# P10_HDMI_Framer.net
KiCad netlist of a schematic drawn in Altium Designer
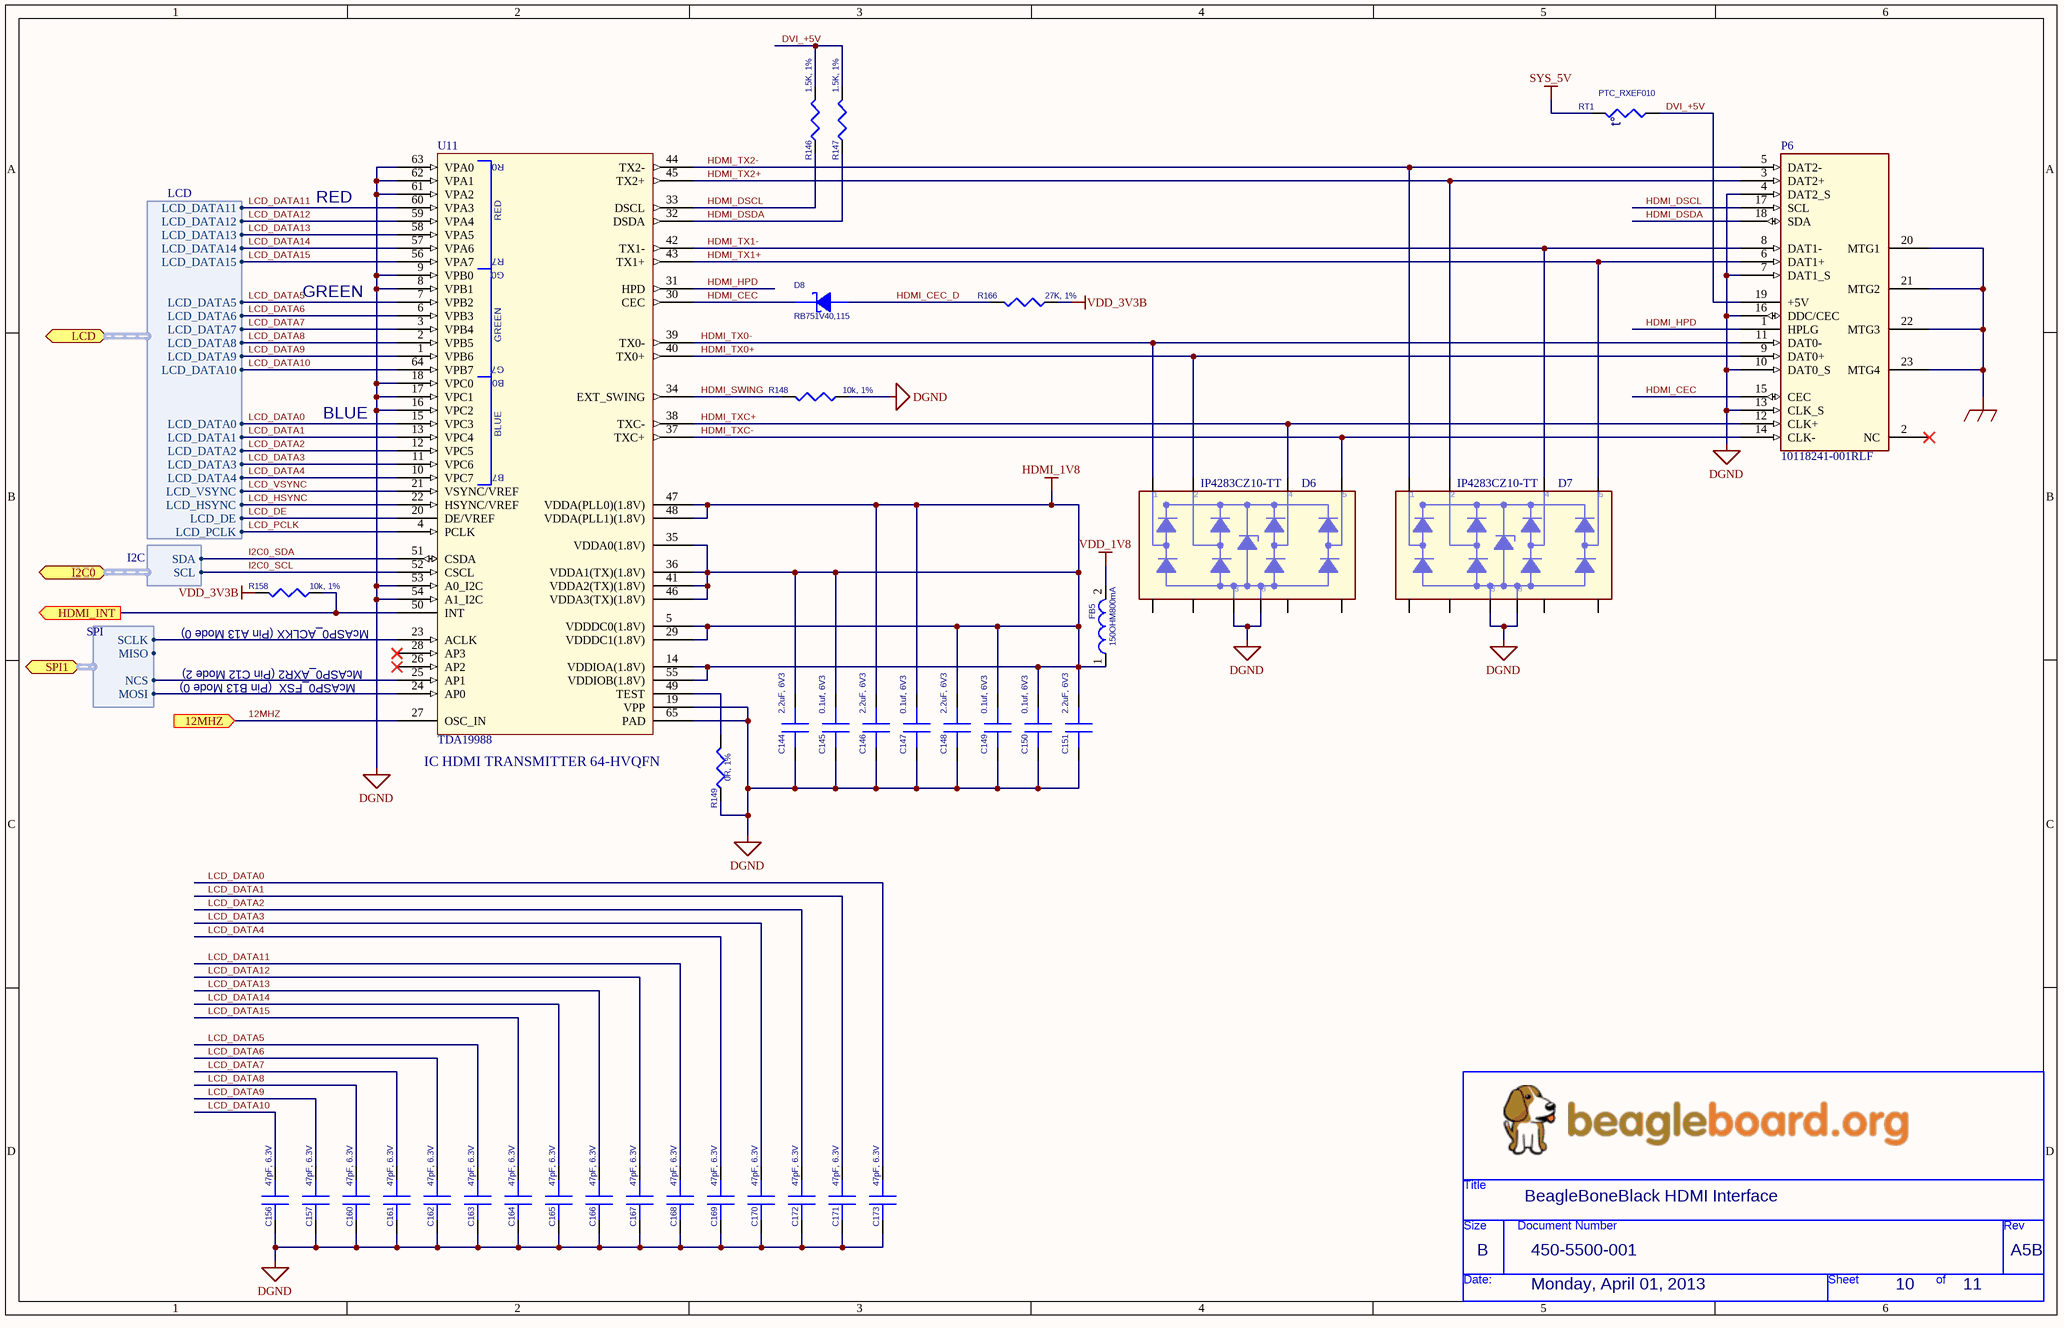
[diagram p0: P10_HDMI Framer.SchDoc]

(export (version "E")
  (design (tool "Eeschema 10.0.6"))
  (components
    (comp (ref "C144")
      (value "2.2uF, 6V3")
      (footprint "402")
      (description "CAP CER 2.2UF 6.3V 10% X5R 0402")
      (fields
        (field (name "MANUFACTURER") "TDK Corporation")
        (field (name "MANUFACTURER PART NUMBER") "C1005X5R0J225K050BC")
      )
      (libsource (lib "BEAGLEBONEBLACK_REV A5B") (part "CAP SMD"))
    )
    (comp (ref "C145")
      (value "0.1uf, 6V3")
      (footprint "402")
      (description "CAP CER 0.1UF 6.3V 10% X5R 0402")
      (fields
        (field (name "MANUFACTURER") "TDK Corporation")
        (field (name "MANUFACTURER PART NUMBER") "C1005X5R0J104K050BA")
      )
      (libsource (lib "BEAGLEBONEBLACK_REV A5B") (part "CAP SMD"))
    )
    (comp (ref "C146")
      (value "2.2uF, 6V3")
      (footprint "402")
      (description "CAP CER 2.2UF 6.3V 10% X5R 0402")
      (fields
        (field (name "MANUFACTURER") "TDK Corporation")
        (field (name "MANUFACTURER PART NUMBER") "C1005X5R0J225K050BC")
      )
      (libsource (lib "BEAGLEBONEBLACK_REV A5B") (part "CAP SMD"))
    )
    (comp (ref "C147")
      (value "0.1uf, 6V3")
      (footprint "402")
      (description "CAP CER 0.1UF 6.3V 10% X5R 0402")
      (fields
        (field (name "MANUFACTURER") "TDK Corporation")
        (field (name "MANUFACTURER PART NUMBER") "C1005X5R0J104K050BA")
      )
      (libsource (lib "BEAGLEBONEBLACK_REV A5B") (part "CAP SMD"))
    )
    (comp (ref "C148")
      (value "2.2uF, 6V3")
      (footprint "402")
      (description "CAP CER 2.2UF 6.3V 10% X5R 0402")
      (fields
        (field (name "MANUFACTURER") "TDK Corporation")
        (field (name "MANUFACTURER PART NUMBER") "C1005X5R0J225K050BC")
      )
      (libsource (lib "BEAGLEBONEBLACK_REV A5B") (part "CAP SMD"))
    )
    (comp (ref "C149")
      (value "0.1uf, 6V3")
      (footprint "402")
      (description "CAP CER 0.1UF 6.3V 10% X5R 0402")
      (fields
        (field (name "MANUFACTURER") "TDK Corporation")
        (field (name "MANUFACTURER PART NUMBER") "C1005X5R0J104K050BA")
      )
      (libsource (lib "BEAGLEBONEBLACK_REV A5B") (part "CAP SMD"))
    )
    (comp (ref "C150")
      (value "0.1uf, 6V3")
      (footprint "402")
      (description "CAP CER 0.1UF 6.3V 10% X5R 0402")
      (fields
        (field (name "MANUFACTURER") "TDK Corporation")
        (field (name "MANUFACTURER PART NUMBER") "C1005X5R0J104K050BA")
      )
      (libsource (lib "BEAGLEBONEBLACK_REV A5B") (part "CAP SMD"))
    )
    (comp (ref "C151")
      (value "2.2uF, 6V3")
      (footprint "402")
      (description "CAP CER 2.2UF 6.3V 10% X5R 0402")
      (fields
        (field (name "MANUFACTURER") "TDK Corporation")
        (field (name "MANUFACTURER PART NUMBER") "C1005X5R0J225K050BC")
      )
      (libsource (lib "BEAGLEBONEBLACK_REV A5B") (part "CAP SMD"))
    )
    (comp (ref "C156")
      (value "47pF, 6.3V")
      (footprint "402")
      (description "CAP CER 47PF 50V 5% NP0 0402")
      (fields
        (field (name "MANUFACTURER") "TDK Corporation")
        (field (name "MANUFACTURER PART NUMBER") "C1005C0G1H470J050BA")
      )
      (libsource (lib "BEAGLEBONEBLACK_REV A5B") (part "CAP SMD"))
    )
    (comp (ref "C157")
      (value "47pF, 6.3V")
      (footprint "402")
      (description "CAP CER 47PF 50V 5% NP0 0402")
      (fields
        (field (name "MANUFACTURER") "TDK Corporation")
        (field (name "MANUFACTURER PART NUMBER") "C1005C0G1H470J050BA")
      )
      (libsource (lib "BEAGLEBONEBLACK_REV A5B") (part "CAP SMD"))
    )
    (comp (ref "C160")
      (value "47pF, 6.3V")
      (footprint "402")
      (description "CAP CER 47PF 50V 5% NP0 0402")
      (fields
        (field (name "MANUFACTURER") "TDK Corporation")
        (field (name "MANUFACTURER PART NUMBER") "C1005C0G1H470J050BA")
      )
      (libsource (lib "BEAGLEBONEBLACK_REV A5B") (part "CAP SMD"))
    )
    (comp (ref "C161")
      (value "47pF, 6.3V")
      (footprint "402")
      (description "CAP CER 47PF 50V 5% NP0 0402")
      (fields
        (field (name "MANUFACTURER") "TDK Corporation")
        (field (name "MANUFACTURER PART NUMBER") "C1005C0G1H470J050BA")
      )
      (libsource (lib "BEAGLEBONEBLACK_REV A5B") (part "CAP SMD"))
    )
    (comp (ref "C162")
      (value "47pF, 6.3V")
      (footprint "402")
      (description "CAP CER 47PF 50V 5% NP0 0402")
      (fields
        (field (name "MANUFACTURER") "TDK Corporation")
        (field (name "MANUFACTURER PART NUMBER") "C1005C0G1H470J050BA")
      )
      (libsource (lib "BEAGLEBONEBLACK_REV A5B") (part "CAP SMD"))
    )
    (comp (ref "C163")
      (value "47pF, 6.3V")
      (footprint "402")
      (description "CAP CER 47PF 50V 5% NP0 0402")
      (fields
        (field (name "MANUFACTURER") "TDK Corporation")
        (field (name "MANUFACTURER PART NUMBER") "C1005C0G1H470J050BA")
      )
      (libsource (lib "BEAGLEBONEBLACK_REV A5B") (part "CAP SMD"))
    )
    (comp (ref "C164")
      (value "47pF, 6.3V")
      (footprint "402")
      (description "CAP CER 47PF 50V 5% NP0 0402")
      (fields
        (field (name "MANUFACTURER") "TDK Corporation")
        (field (name "MANUFACTURER PART NUMBER") "C1005C0G1H470J050BA")
      )
      (libsource (lib "BEAGLEBONEBLACK_REV A5B") (part "CAP SMD"))
    )
    (comp (ref "C165")
      (value "47pF, 6.3V")
      (footprint "402")
      (description "CAP CER 47PF 50V 5% NP0 0402")
      (fields
        (field (name "MANUFACTURER") "TDK Corporation")
        (field (name "MANUFACTURER PART NUMBER") "C1005C0G1H470J050BA")
      )
      (libsource (lib "BEAGLEBONEBLACK_REV A5B") (part "CAP SMD"))
    )
    (comp (ref "C166")
      (value "47pF, 6.3V")
      (footprint "402")
      (description "CAP CER 47PF 50V 5% NP0 0402")
      (fields
        (field (name "MANUFACTURER") "TDK Corporation")
        (field (name "MANUFACTURER PART NUMBER") "C1005C0G1H470J050BA")
      )
      (libsource (lib "BEAGLEBONEBLACK_REV A5B") (part "CAP SMD"))
    )
    (comp (ref "C167")
      (value "47pF, 6.3V")
      (footprint "402")
      (description "CAP CER 47PF 50V 5% NP0 0402")
      (fields
        (field (name "MANUFACTURER") "TDK Corporation")
        (field (name "MANUFACTURER PART NUMBER") "C1005C0G1H470J050BA")
      )
      (libsource (lib "BEAGLEBONEBLACK_REV A5B") (part "CAP SMD"))
    )
    (comp (ref "C168")
      (value "47pF, 6.3V")
      (footprint "402")
      (description "CAP CER 47PF 50V 5% NP0 0402")
      (fields
        (field (name "MANUFACTURER") "TDK Corporation")
        (field (name "MANUFACTURER PART NUMBER") "C1005C0G1H470J050BA")
      )
      (libsource (lib "BEAGLEBONEBLACK_REV A5B") (part "CAP SMD"))
    )
    (comp (ref "C169")
      (value "47pF, 6.3V")
      (footprint "402")
      (description "CAP CER 47PF 50V 5% NP0 0402")
      (fields
        (field (name "MANUFACTURER") "TDK Corporation")
        (field (name "MANUFACTURER PART NUMBER") "C1005C0G1H470J050BA")
      )
      (libsource (lib "BEAGLEBONEBLACK_REV A5B") (part "CAP SMD"))
    )
    (comp (ref "C170")
      (value "47pF, 6.3V")
      (footprint "402")
      (description "CAP CER 47PF 50V 5% NP0 0402")
      (fields
        (field (name "MANUFACTURER") "TDK Corporation")
        (field (name "MANUFACTURER PART NUMBER") "C1005C0G1H470J050BA")
      )
      (libsource (lib "BEAGLEBONEBLACK_REV A5B") (part "CAP SMD"))
    )
    (comp (ref "C171")
      (value "47pF, 6.3V")
      (footprint "402")
      (description "CAP CER 47PF 50V 5% NP0 0402")
      (fields
        (field (name "MANUFACTURER") "TDK Corporation")
        (field (name "MANUFACTURER PART NUMBER") "C1005C0G1H470J050BA")
      )
      (libsource (lib "BEAGLEBONEBLACK_REV A5B") (part "CAP SMD"))
    )
    (comp (ref "C172")
      (value "47pF, 6.3V")
      (footprint "402")
      (description "CAP CER 47PF 50V 5% NP0 0402")
      (fields
        (field (name "MANUFACTURER") "TDK Corporation")
        (field (name "MANUFACTURER PART NUMBER") "C1005C0G1H470J050BA")
      )
      (libsource (lib "BEAGLEBONEBLACK_REV A5B") (part "CAP SMD"))
    )
    (comp (ref "C173")
      (value "47pF, 6.3V")
      (footprint "402")
      (description "CAP CER 47PF 50V 5% NP0 0402")
      (fields
        (field (name "MANUFACTURER") "TDK Corporation")
        (field (name "MANUFACTURER PART NUMBER") "C1005C0G1H470J050BA")
      )
      (libsource (lib "BEAGLEBONEBLACK_REV A5B") (part "CAP SMD"))
    )
    (comp (ref "D6")
      (value "IP4283CZ10-TT")
      (footprint "TSSOP10")
      (description "DIODE ESD PROT HDMI 10TSSOP")
      (fields
        (field (name "MANUFACTURER") "NXP Semiconductors")
        (field (name "MANUFACTURER PART NUMBER") "IP4283CZ10-TT,118")
      )
      (libsource (lib "BEAGLEBONEBLACK_REV A5B") (part "32CTQ030/TO_1"))
    )
    (comp (ref "D7")
      (value "IP4283CZ10-TT")
      (footprint "TSSOP10")
      (description "DIODE ESD PROT HDMI 10TSSOP")
      (fields
        (field (name "MANUFACTURER") "NXP Semiconductors")
        (field (name "MANUFACTURER PART NUMBER") "IP4283CZ10-TT,118")
      )
      (libsource (lib "BEAGLEBONEBLACK_REV A5B") (part "32CTQ030/TO_1"))
    )
    (comp (ref "D8")
      (value "RB751V40,115")
      (footprint "SOD323")
      (description "DIODE SCHOTTKY 40V 120MA SOD323")
      (fields (field (name "MANUFACTURER") "NXP Semiconductors"))
      (libsource (lib "BEAGLEBONEBLACK_REV A5B") (part "Zener"))
    )
    (comp (ref "FB5")
      (value "150OHM800mA")
      (footprint "SM-7351-IND-0805")
      (description "FERRITE 800MA 150 OHM 0805 SMD")
      (fields
        (field (name "MANUFACTURER") "Laird-Signal Integrity Products")
        (field (name "MANUFACTURER PART NUMBER") "LI0805H151R-10")
      )
      (libsource (lib "BEAGLEBONEBLACK_REV A5B") (part "IND"))
    )
    (comp (ref "P6")
      (value "10118241-001RLF")
      (footprint "CONN19_HDMI")
      (description "CONN HDMI RECPT 19POS SMT R/A")
      (fields (field (name "MANUFACTURER") "FCI"))
      (libsource (lib "BEAGLEBONEBLACK_REV A5B") (part "Micro HDMI"))
    )
    (comp (ref "R146")
      (value "1.5K, 1%")
      (footprint "402")
      (description "RES 1.50K OHM 1/16W 1% 0402 SMD")
      (fields
        (field (name "MANUFACTURER") "Yageo")
        (field (name "MANUFACTURER PART NUMBER") "RC0402FR-071K5L")
      )
      (libsource (lib "BEAGLEBONEBLACK_REV A5B") (part "RES SMD"))
    )
    (comp (ref "R147")
      (value "1.5K, 1%")
      (footprint "402")
      (description "RES 1.50K OHM 1/16W 1% 0402 SMD")
      (fields
        (field (name "MANUFACTURER") "Yageo")
        (field (name "MANUFACTURER PART NUMBER") "RC0402FR-071K5L")
      )
      (libsource (lib "BEAGLEBONEBLACK_REV A5B") (part "RES SMD"))
    )
    (comp (ref "R148")
      (value "10k, 1%")
      (footprint "402")
      (description "RES 10K OHM 1/16W 5% 0402 SMD")
      (fields
        (field (name "MANUFACTURER") "Rohm Semiconductor")
        (field (name "MANUFACTURER PART NUMBER") "MCR01MZPJ103")
      )
      (libsource (lib "BEAGLEBONEBLACK_REV A5B") (part "RES SMD"))
    )
    (comp (ref "R149")
      (value "0R, 1%")
      (footprint "402")
      (description "RES 0.0 OHM 1/16W 0402 SMD")
      (fields
        (field (name "MANUFACTURER") "Yageo")
        (field (name "MANUFACTURER PART NUMBER") "RC0402JR-070RL")
      )
      (libsource (lib "BEAGLEBONEBLACK_REV A5B") (part "RES SMD"))
    )
    (comp (ref "R158")
      (value "10k, 1%")
      (footprint "402")
      (description "RES 10K OHM 1/16W 5% 0402 SMD")
      (fields
        (field (name "MANUFACTURER") "Rohm Semiconductor")
        (field (name "MANUFACTURER PART NUMBER") "MCR01MZPJ103")
      )
      (libsource (lib "BEAGLEBONEBLACK_REV A5B") (part "RES SMD"))
    )
    (comp (ref "R166")
      (value "27K, 1%")
      (footprint "402")
      (description "RES 27.0K OHM 1/16W 1% 0402 SMD")
      (fields
        (field (name "MANUFACTURER") "Yageo")
        (field (name "MANUFACTURER PART NUMBER") "RC0402FR-0727KL")
      )
      (libsource (lib "BEAGLEBONEBLACK_REV A5B") (part "RES SMD"))
    )
    (comp (ref "RT1")
      (value "PTC_RXEF010")
      (footprint "POLYSW200-5638-310")
      (description "POLYSWITCH PTC RESET 0.1A")
      (fields
        (field (name "MANUFACTURER") "TE Connectivity")
        (field (name "MANUFACTURER PART NUMBER") "RXEF010")
      )
      (libsource (lib "BEAGLEBONEBLACK_REV A5B") (part "PTC"))
    )
    (comp (ref "U11")
      (value "TDA19988")
      (footprint "QFN64S9X9P5")
      (description "IC HDMI TRANSMITTER 64-HVQFN")
      (fields
        (field (name "MANUFACTURER") "NXP Semiconductors")
        (field (name "MANUFACTURER PART NUMBER") "TDA19988AHN/C1,551")
      )
      (libsource (lib "BEAGLEBONEBLACK_REV A5B") (part "TDA19988"))
    )
  )
  (nets
    (net (code "4") (name "/12MHZ") (class "Default")
      (node (ref "U11") (pin "27") (pinfunction "OSC_IN_27") (pintype "passive"))
    )
    (net (code "5") (name "/DVI_+5V") (class "Default")
      (node (ref "P6") (pin "19") (pinfunction "+5V_19") (pintype "power_in"))
      (node (ref "R146") (pin "1") (pinfunction "P1_1") (pintype "passive"))
      (node (ref "R147") (pin "1") (pinfunction "P1_1") (pintype "passive"))
      (node (ref "RT1") (pin "2") (pinfunction "P2_2") (pintype "passive"))
    )
    (net (code "6") (name "/HDMI_CEC") (class "Default")
      (node (ref "D8") (pin "1") (pinfunction "C_1") (pintype "passive"))
      (node (ref "P6") (pin "15") (pinfunction "CEC_15") (pintype "bidirectional"))
      (node (ref "U11") (pin "30") (pinfunction "CEC_30") (pintype "output"))
    )
    (net (code "7") (name "/HDMI_CEC_D") (class "Default")
      (node (ref "D8") (pin "2") (pinfunction "A_2") (pintype "passive"))
      (node (ref "R166") (pin "1") (pinfunction "P1_1") (pintype "passive"))
    )
    (net (code "8") (name "/HDMI_DSCL") (class "Default")
      (node (ref "P6") (pin "17") (pinfunction "SCL_17") (pintype "input"))
      (node (ref "R146") (pin "2") (pinfunction "P2_2") (pintype "passive"))
      (node (ref "U11") (pin "33") (pinfunction "DSCL_33") (pintype "output"))
    )
    (net (code "9") (name "/HDMI_DSDA") (class "Default")
      (node (ref "P6") (pin "18") (pinfunction "SDA_18") (pintype "bidirectional"))
      (node (ref "R147") (pin "2") (pinfunction "P2_2") (pintype "passive"))
      (node (ref "U11") (pin "32") (pinfunction "DSDA_32") (pintype "output"))
    )
    (net (code "10") (name "/HDMI_HPD") (class "Default")
      (node (ref "P6") (pin "1") (pinfunction "HPLG_1") (pintype "passive"))
      (node (ref "U11") (pin "31") (pinfunction "HPD_31") (pintype "output"))
    )
    (net (code "11") (name "/HDMI_INT") (class "Default")
      (node (ref "R158") (pin "2") (pinfunction "P2_2") (pintype "passive"))
      (node (ref "U11") (pin "50") (pinfunction "INT_50") (pintype "open_collector"))
    )
    (net (code "12") (name "/HDMI_SWING") (class "Default")
      (node (ref "R148") (pin "1") (pinfunction "P1_1") (pintype "passive"))
      (node (ref "U11") (pin "34") (pinfunction "EXT_SWING_34") (pintype "output"))
    )
    (net (code "13") (name "/HDMI_TX0+") (class "Default")
      (node (ref "D6") (pin "2") (pinfunction "2_2") (pintype "passive"))
      (node (ref "P6") (pin "9") (pinfunction "DAT0+_9") (pintype "input"))
      (node (ref "U11") (pin "40") (pinfunction "TX0+_40") (pintype "output"))
    )
    (net (code "14") (name "/HDMI_TX0-") (class "Default")
      (node (ref "D6") (pin "1") (pinfunction "1_1") (pintype "passive"))
      (node (ref "P6") (pin "11") (pinfunction "DAT0-_11") (pintype "input"))
      (node (ref "U11") (pin "39") (pinfunction "TX0-_39") (pintype "output"))
    )
    (net (code "15") (name "/HDMI_TX1+") (class "Default")
      (node (ref "D7") (pin "5") (pinfunction "5_5") (pintype "passive"))
      (node (ref "P6") (pin "6") (pinfunction "DAT1+_6") (pintype "input"))
      (node (ref "U11") (pin "43") (pinfunction "TX1+_43") (pintype "output"))
    )
    (net (code "16") (name "/HDMI_TX1-") (class "Default")
      (node (ref "D7") (pin "4") (pinfunction "4_4") (pintype "passive"))
      (node (ref "P6") (pin "8") (pinfunction "DAT1-_8") (pintype "input"))
      (node (ref "U11") (pin "42") (pinfunction "TX1-_42") (pintype "output"))
    )
    (net (code "17") (name "/HDMI_TX2+") (class "Default")
      (node (ref "D7") (pin "2") (pinfunction "2_2") (pintype "passive"))
      (node (ref "P6") (pin "3") (pinfunction "DAT2+_3") (pintype "input"))
      (node (ref "U11") (pin "45") (pinfunction "TX2+_45") (pintype "output"))
    )
    (net (code "18") (name "/HDMI_TX2-") (class "Default")
      (node (ref "D7") (pin "1") (pinfunction "1_1") (pintype "passive"))
      (node (ref "P6") (pin "5") (pinfunction "DAT2-_5") (pintype "input"))
      (node (ref "U11") (pin "44") (pinfunction "TX2-_44") (pintype "output"))
    )
    (net (code "19") (name "/HDMI_TXC+") (class "Default")
      (node (ref "D6") (pin "4") (pinfunction "4_4") (pintype "passive"))
      (node (ref "P6") (pin "12") (pinfunction "CLK+_12") (pintype "input"))
      (node (ref "U11") (pin "38") (pinfunction "TXC-_38") (pintype "output"))
    )
    (net (code "20") (name "/HDMI_TXC-") (class "Default")
      (node (ref "D6") (pin "5") (pinfunction "5_5") (pintype "passive"))
      (node (ref "P6") (pin "14") (pinfunction "CLK-_14") (pintype "input"))
      (node (ref "U11") (pin "37") (pinfunction "TXC+_37") (pintype "output"))
    )
    (net (code "21") (name "/I2C0_SCL") (class "Default")
      (node (ref "U11") (pin "52") (pinfunction "CSCL_52") (pintype "input"))
    )
    (net (code "22") (name "/I2C0_SDA") (class "Default")
      (node (ref "U11") (pin "51") (pinfunction "CSDA_51") (pintype "bidirectional"))
    )
    (net (code "23") (name "/LCD_DATA0") (class "Default")
      (node (ref "C173") (pin "1") (pinfunction "1_1") (pintype "passive"))
      (node (ref "U11") (pin "15") (pinfunction "VPC3_15") (pintype "input"))
    )
    (net (code "24") (name "/LCD_DATA1") (class "Default")
      (node (ref "C171") (pin "1") (pinfunction "1_1") (pintype "passive"))
      (node (ref "U11") (pin "13") (pinfunction "VPC4_13") (pintype "input"))
    )
    (net (code "25") (name "/LCD_DATA2") (class "Default")
      (node (ref "C172") (pin "1") (pinfunction "1_1") (pintype "passive"))
      (node (ref "U11") (pin "12") (pinfunction "VPC5_12") (pintype "input"))
    )
    (net (code "26") (name "/LCD_DATA3") (class "Default")
      (node (ref "C170") (pin "1") (pinfunction "1_1") (pintype "passive"))
      (node (ref "U11") (pin "11") (pinfunction "VPC6_11") (pintype "input"))
    )
    (net (code "27") (name "/LCD_DATA4") (class "Default")
      (node (ref "C169") (pin "1") (pinfunction "1_1") (pintype "passive"))
      (node (ref "U11") (pin "10") (pinfunction "VPC7_10") (pintype "input"))
    )
    (net (code "28") (name "/LCD_DATA5") (class "Default")
      (node (ref "C163") (pin "1") (pinfunction "1_1") (pintype "passive"))
      (node (ref "U11") (pin "7") (pinfunction "VPB2_7") (pintype "input"))
    )
    (net (code "29") (name "/LCD_DATA6") (class "Default")
      (node (ref "C162") (pin "1") (pinfunction "1_1") (pintype "passive"))
      (node (ref "U11") (pin "6") (pinfunction "VPB3_6") (pintype "input"))
    )
    (net (code "30") (name "/LCD_DATA7") (class "Default")
      (node (ref "C161") (pin "1") (pinfunction "1_1") (pintype "passive"))
      (node (ref "U11") (pin "3") (pinfunction "VPB4_3") (pintype "input"))
    )
    (net (code "31") (name "/LCD_DATA8") (class "Default")
      (node (ref "C160") (pin "1") (pinfunction "1_1") (pintype "passive"))
      (node (ref "U11") (pin "2") (pinfunction "VPB5_2") (pintype "input"))
    )
    (net (code "32") (name "/LCD_DATA9") (class "Default")
      (node (ref "C157") (pin "1") (pinfunction "1_1") (pintype "passive"))
      (node (ref "U11") (pin "1") (pinfunction "VPB6_1") (pintype "input"))
    )
    (net (code "33") (name "/LCD_DATA10") (class "Default")
      (node (ref "C156") (pin "1") (pinfunction "1_1") (pintype "passive"))
      (node (ref "U11") (pin "64") (pinfunction "VPB7_64") (pintype "input"))
    )
    (net (code "34") (name "/LCD_DATA11") (class "Default")
      (node (ref "C168") (pin "1") (pinfunction "1_1") (pintype "passive"))
      (node (ref "U11") (pin "60") (pinfunction "VPA3_60") (pintype "input"))
    )
    (net (code "35") (name "/LCD_DATA12") (class "Default")
      (node (ref "C167") (pin "1") (pinfunction "1_1") (pintype "passive"))
      (node (ref "U11") (pin "59") (pinfunction "VPA4_59") (pintype "input"))
    )
    (net (code "36") (name "/LCD_DATA13") (class "Default")
      (node (ref "C166") (pin "1") (pinfunction "1_1") (pintype "passive"))
      (node (ref "U11") (pin "58") (pinfunction "VPA5_58") (pintype "input"))
    )
    (net (code "37") (name "/LCD_DATA14") (class "Default")
      (node (ref "C165") (pin "1") (pinfunction "1_1") (pintype "passive"))
      (node (ref "U11") (pin "57") (pinfunction "VPA6_57") (pintype "input"))
    )
    (net (code "38") (name "/LCD_DATA15") (class "Default")
      (node (ref "C164") (pin "1") (pinfunction "1_1") (pintype "passive"))
      (node (ref "U11") (pin "56") (pinfunction "VPA7_56") (pintype "input"))
    )
    (net (code "39") (name "/LCD_DE") (class "Default")
      (node (ref "U11") (pin "20") (pinfunction "DE/VREF_20") (pintype "passive"))
    )
    (net (code "40") (name "/LCD_HSYNC") (class "Default")
      (node (ref "U11") (pin "22") (pinfunction "HSYNC/VREF_22") (pintype "input"))
    )
    (net (code "41") (name "/LCD_PCLK") (class "Default")
      (node (ref "U11") (pin "4") (pinfunction "PCLK_4") (pintype "input"))
    )
    (net (code "42") (name "/LCD_VSYNC") (class "Default")
      (node (ref "U11") (pin "21") (pinfunction "VSYNC/VREF_21") (pintype "input"))
    )
    (net (code "43") (name "/MOSI") (class "Default")
      (node (ref "U11") (pin "24") (pinfunction "AP0_24") (pintype "input"))
    )
    (net (code "44") (name "/NCS") (class "Default")
      (node (ref "U11") (pin "25") (pinfunction "AP1_25") (pintype "input"))
    )
    (net (code "45") (name "/SCLK") (class "Default")
      (node (ref "U11") (pin "23") (pinfunction "ACLK_23") (pintype "input"))
    )
    (net (code "49") (name "DGND") (class "Default")
      (node (ref "C144") (pin "2") (pinfunction "2_2") (pintype "passive"))
      (node (ref "C145") (pin "2") (pinfunction "2_2") (pintype "passive"))
      (node (ref "C146") (pin "2") (pinfunction "2_2") (pintype "passive"))
      (node (ref "C147") (pin "2") (pinfunction "2_2") (pintype "passive"))
      (node (ref "C148") (pin "2") (pinfunction "2_2") (pintype "passive"))
      (node (ref "C149") (pin "2") (pinfunction "2_2") (pintype "passive"))
      (node (ref "C150") (pin "2") (pinfunction "2_2") (pintype "passive"))
      (node (ref "C151") (pin "2") (pinfunction "2_2") (pintype "passive"))
      (node (ref "C156") (pin "2") (pinfunction "2_2") (pintype "passive"))
      (node (ref "C157") (pin "2") (pinfunction "2_2") (pintype "passive"))
      (node (ref "C160") (pin "2") (pinfunction "2_2") (pintype "passive"))
      (node (ref "C161") (pin "2") (pinfunction "2_2") (pintype "passive"))
      (node (ref "C162") (pin "2") (pinfunction "2_2") (pintype "passive"))
      (node (ref "C163") (pin "2") (pinfunction "2_2") (pintype "passive"))
      (node (ref "C164") (pin "2") (pinfunction "2_2") (pintype "passive"))
      (node (ref "C165") (pin "2") (pinfunction "2_2") (pintype "passive"))
      (node (ref "C166") (pin "2") (pinfunction "2_2") (pintype "passive"))
      (node (ref "C167") (pin "2") (pinfunction "2_2") (pintype "passive"))
      (node (ref "C168") (pin "2") (pinfunction "2_2") (pintype "passive"))
      (node (ref "C169") (pin "2") (pinfunction "2_2") (pintype "passive"))
      (node (ref "C170") (pin "2") (pinfunction "2_2") (pintype "passive"))
      (node (ref "C171") (pin "2") (pinfunction "2_2") (pintype "passive"))
      (node (ref "C172") (pin "2") (pinfunction "2_2") (pintype "passive"))
      (node (ref "C173") (pin "2") (pinfunction "2_2") (pintype "passive"))
      (node (ref "D6") (pin "3") (pinfunction "3_3") (pintype "passive"))
      (node (ref "D6") (pin "8") (pinfunction "8_8") (pintype "passive"))
      (node (ref "D7") (pin "3") (pinfunction "3_3") (pintype "passive"))
      (node (ref "D7") (pin "8") (pinfunction "8_8") (pintype "passive"))
      (node (ref "P6") (pin "10") (pinfunction "DAT0_S_10") (pintype "input"))
      (node (ref "P6") (pin "13") (pinfunction "CLK_S_13") (pintype "input"))
      (node (ref "P6") (pin "16") (pinfunction "DDC/CEC_16") (pintype "bidirectional"))
      (node (ref "P6") (pin "4") (pinfunction "DAT2_S_4") (pintype "input"))
      (node (ref "P6") (pin "7") (pinfunction "DAT1_S_7") (pintype "input"))
      (node (ref "R148") (pin "2") (pinfunction "P2_2") (pintype "passive"))
      (node (ref "R149") (pin "2") (pinfunction "P2_2") (pintype "passive"))
      (node (ref "U11") (pin "16") (pinfunction "VPC2_16") (pintype "input"))
      (node (ref "U11") (pin "17") (pinfunction "VPC1_17") (pintype "input"))
      (node (ref "U11") (pin "18") (pinfunction "VPC0_18") (pintype "input"))
      (node (ref "U11") (pin "19") (pinfunction "VPP_19") (pintype "power_in"))
      (node (ref "U11") (pin "53") (pinfunction "A0_I2C_53") (pintype "input"))
      (node (ref "U11") (pin "54") (pinfunction "A1_I2C_54") (pintype "input"))
      (node (ref "U11") (pin "61") (pinfunction "VPA2_61") (pintype "input"))
      (node (ref "U11") (pin "62") (pinfunction "VPA1_62") (pintype "input"))
      (node (ref "U11") (pin "63") (pinfunction "VPA0_63") (pintype "input"))
      (node (ref "U11") (pin "65") (pinfunction "PAD_65") (pintype "power_in"))
      (node (ref "U11") (pin "8") (pinfunction "VPB1_8") (pintype "input"))
      (node (ref "U11") (pin "9") (pinfunction "VPB0_9") (pintype "input"))
    )
    (net (code "50") (name "GND_EARTH") (class "Default")
      (node (ref "P6") (pin "20") (pinfunction "MTG1_20") (pintype "passive"))
      (node (ref "P6") (pin "21") (pinfunction "MTG2_21") (pintype "passive"))
      (node (ref "P6") (pin "22") (pinfunction "MTG3_22") (pintype "passive"))
      (node (ref "P6") (pin "23") (pinfunction "MTG4_23") (pintype "passive"))
    )
    (net (code "51") (name "HDMI_1V8") (class "Default")
      (node (ref "C144") (pin "1") (pinfunction "1_1") (pintype "passive"))
      (node (ref "C145") (pin "1") (pinfunction "1_1") (pintype "passive"))
      (node (ref "C146") (pin "1") (pinfunction "1_1") (pintype "passive"))
      (node (ref "C147") (pin "1") (pinfunction "1_1") (pintype "passive"))
      (node (ref "C148") (pin "1") (pinfunction "1_1") (pintype "passive"))
      (node (ref "C149") (pin "1") (pinfunction "1_1") (pintype "passive"))
      (node (ref "C150") (pin "1") (pinfunction "1_1") (pintype "passive"))
      (node (ref "C151") (pin "1") (pinfunction "1_1") (pintype "passive"))
      (node (ref "FB5") (pin "1") (pinfunction "1_1") (pintype "passive"))
      (node (ref "U11") (pin "14") (pinfunction "VDDIOA(1.8V)_14") (pintype "power_in"))
      (node (ref "U11") (pin "29") (pinfunction "VDDDC1(1.8V)_29") (pintype "power_in"))
      (node (ref "U11") (pin "35") (pinfunction "VDDA0(1.8V)_35") (pintype "power_in"))
      (node (ref "U11") (pin "36") (pinfunction "VDDA1(TX)(1.8V)_36") (pintype "power_in"))
      (node (ref "U11") (pin "41") (pinfunction "VDDA2(TX)(1.8V)_41") (pintype "power_in"))
      (node (ref "U11") (pin "46") (pinfunction "VDDA3(TX)(1.8V)_46") (pintype "power_in"))
      (node (ref "U11") (pin "47") (pinfunction "VDDA(PLL0)(1.8V)_47") (pintype "power_in"))
      (node (ref "U11") (pin "48") (pinfunction "VDDA(PLL1)(1.8V)_48") (pintype "power_in"))
      (node (ref "U11") (pin "5") (pinfunction "VDDDC0(1.8V)_5") (pintype "power_in"))
      (node (ref "U11") (pin "55") (pinfunction "VDDIOB(1.8V)_55") (pintype "power_in"))
    )
    (net (code "52") (name "Net-(R149-P1)") (class "Default")
      (node (ref "R149") (pin "1") (pinfunction "P1_1") (pintype "passive"))
      (node (ref "U11") (pin "49") (pinfunction "TEST_49") (pintype "passive"))
    )
    (net (code "53") (name "SYS_5V") (class "Default")
      (node (ref "RT1") (pin "1") (pinfunction "P1_1") (pintype "passive"))
    )
    (net (code "54") (name "VDD_1V8") (class "Default")
      (node (ref "FB5") (pin "2") (pinfunction "2_2") (pintype "passive"))
    )
    (net (code "55") (name "VDD_3V3B") (class "Default")
      (node (ref "R158") (pin "1") (pinfunction "P1_1") (pintype "passive"))
      (node (ref "R166") (pin "2") (pinfunction "P2_2") (pintype "passive"))
    )
    (net (code "56") (name "unconnected-(D6-Pad6)") (class "Default")
      (node (ref "D6") (pin "6") (pinfunction "6_6") (pintype "passive"))
    )
    (net (code "57") (name "unconnected-(D6-Pad7)") (class "Default")
      (node (ref "D6") (pin "7") (pinfunction "7_7") (pintype "passive"))
    )
    (net (code "58") (name "unconnected-(D6-Pad9)") (class "Default")
      (node (ref "D6") (pin "9") (pinfunction "9_9") (pintype "passive"))
    )
    (net (code "59") (name "unconnected-(D6-Pad10)") (class "Default")
      (node (ref "D6") (pin "10") (pinfunction "10_10") (pintype "passive"))
    )
    (net (code "60") (name "unconnected-(D7-Pad6)") (class "Default")
      (node (ref "D7") (pin "6") (pinfunction "6_6") (pintype "passive"))
    )
    (net (code "61") (name "unconnected-(D7-Pad7)") (class "Default")
      (node (ref "D7") (pin "7") (pinfunction "7_7") (pintype "passive"))
    )
    (net (code "62") (name "unconnected-(D7-Pad9)") (class "Default")
      (node (ref "D7") (pin "9") (pinfunction "9_9") (pintype "passive"))
    )
    (net (code "63") (name "unconnected-(D7-Pad10)") (class "Default")
      (node (ref "D7") (pin "10") (pinfunction "10_10") (pintype "passive"))
    )
    (net (code "64") (name "unconnected-(P6-NC-Pad2)") (class "Default")
      (node (ref "P6") (pin "2") (pinfunction "NC_2") (pintype "passive+no_connect"))
    )
    (net (code "65") (name "unconnected-(U11-AP2-Pad26)") (class "Default")
      (node (ref "U11") (pin "26") (pinfunction "AP2_26") (pintype "input+no_connect"))
    )
    (net (code "66") (name "unconnected-(U11-AP3-Pad28)") (class "Default")
      (node (ref "U11") (pin "28") (pinfunction "AP3_28") (pintype "input+no_connect"))
    )
  )
)
